# interface-board.net
KiCad netlist of a schematic drawn in EAGLE
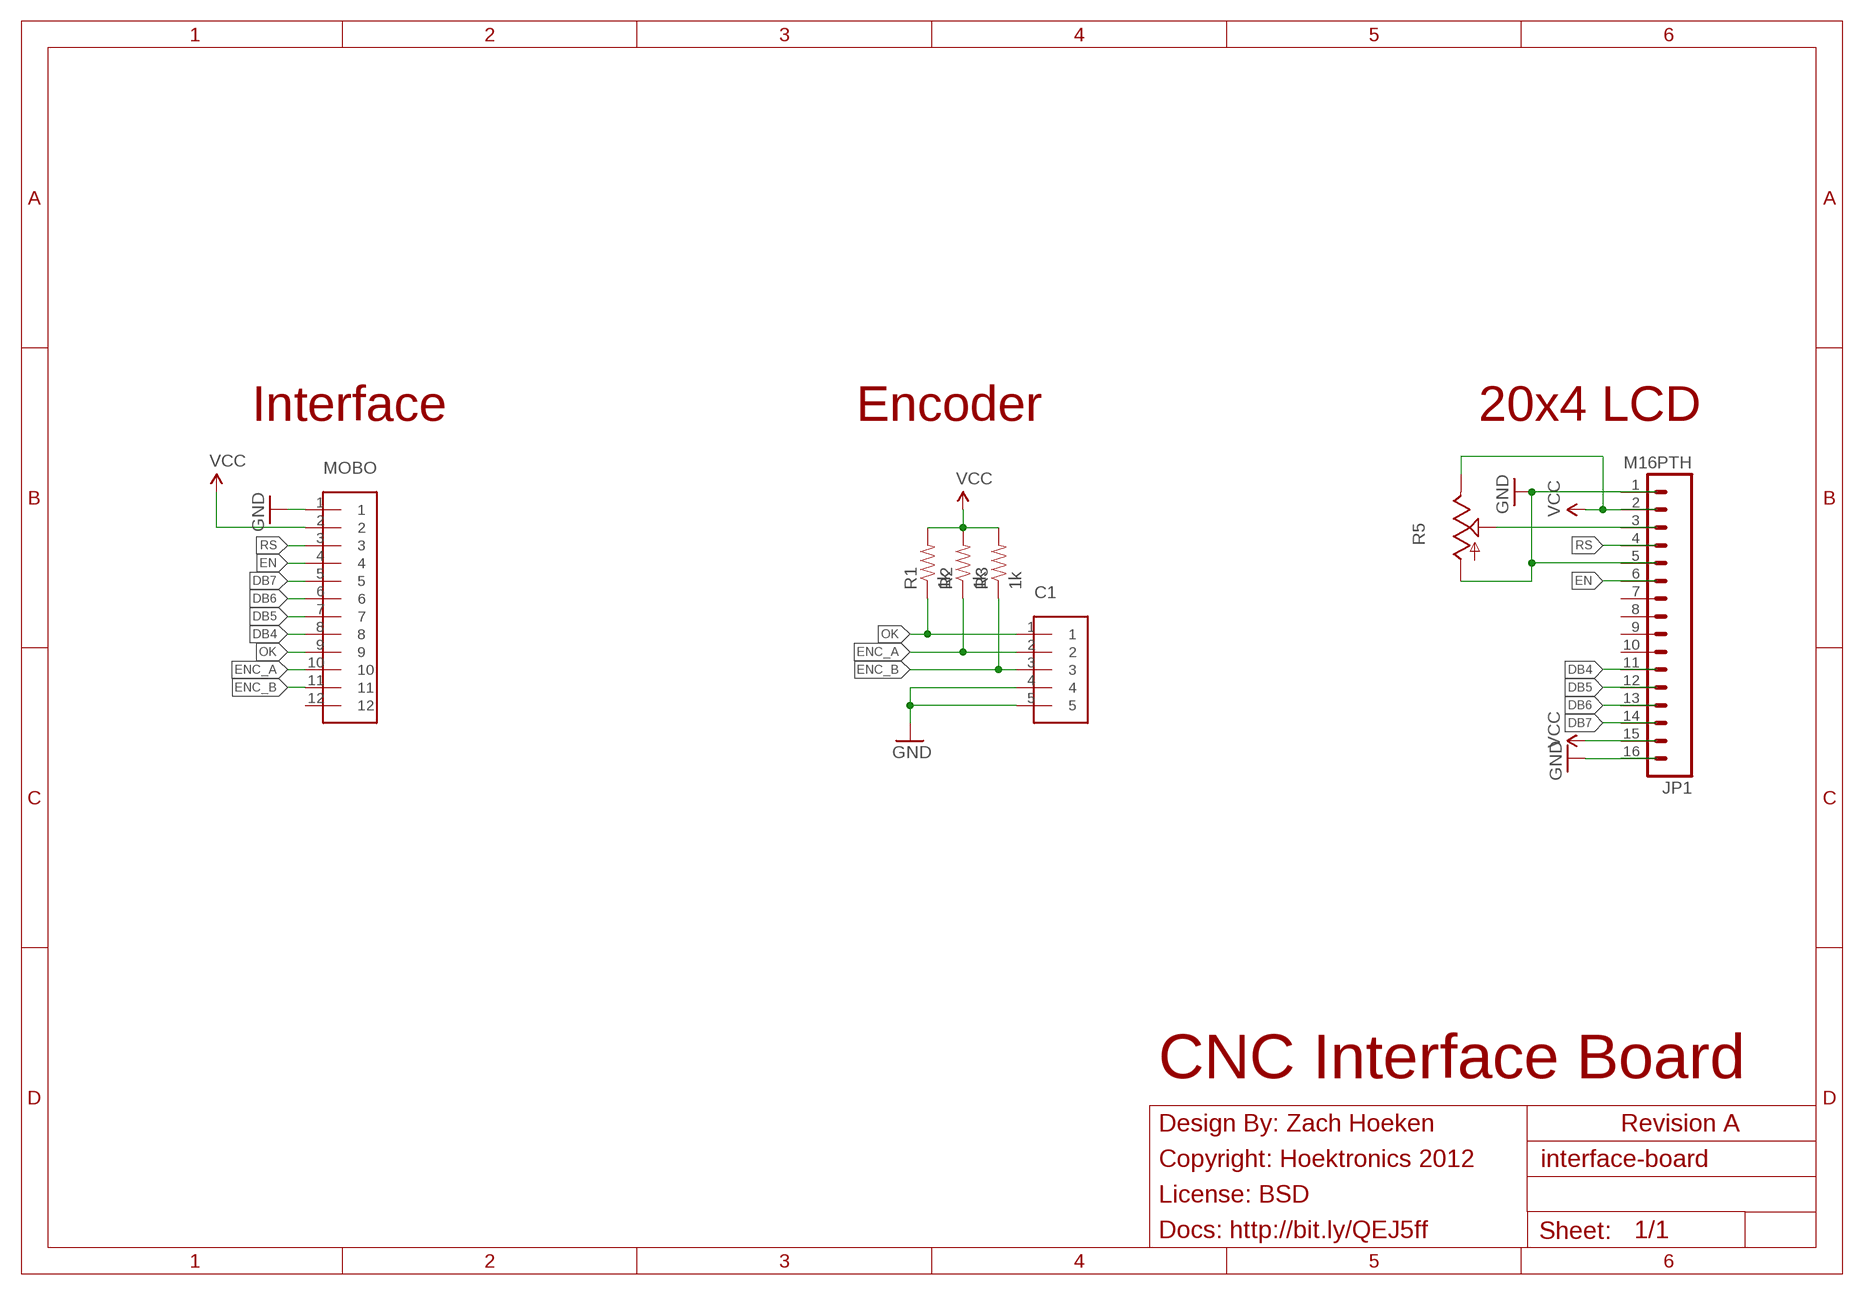
[diagram p0: schematic, sheet 1]

(export (version "E")
  (design (tool "Eeschema 10.0.6"))
  (components
    (comp (ref "C1")
      (value "CONN-5")
      (footprint "eagle-import:XH-5")
      (libsource (lib "eagle-import") (part "CONN-5"))
    )
    (comp (ref "JP1")
      (value "M16PTH")
      (footprint "eagle-import:1X16")
      (libsource (lib "eagle-import") (part "M16PTH"))
    )
    (comp (ref "MOBO")
      (value "CONN-12")
      (footprint "eagle-import:XH-12")
      (libsource (lib "eagle-import") (part "CONN-12"))
    )
    (comp (ref "R1")
      (value "1k")
      (footprint "eagle-import:0805-RC")
      (libsource (lib "eagle-import") (part "RESISTOR0805"))
    )
    (comp (ref "R2")
      (value "1k")
      (footprint "eagle-import:0805-RC")
      (libsource (lib "eagle-import") (part "RESISTOR0805"))
    )
    (comp (ref "R3")
      (value "1k")
      (footprint "eagle-import:0805-RC")
      (libsource (lib "eagle-import") (part "RESISTOR0805"))
    )
    (comp (ref "R5")
      (value "TRIM_US-B25P")
      (footprint "eagle-import:B25P")
      (libsource (lib "eagle-import") (part "TRIM_US-B25P"))
    )
  )
  (nets
    (net (code "1") (name "DB4") (class "Default")
      (node (ref "JP1") (pin "11") (pinfunction "11_11") (pintype "passive"))
      (node (ref "MOBO") (pin "8") (pinfunction "8_8") (pintype "bidirectional"))
    )
    (net (code "2") (name "DB5") (class "Default")
      (node (ref "JP1") (pin "12") (pinfunction "12_12") (pintype "passive"))
      (node (ref "MOBO") (pin "7") (pinfunction "7_7") (pintype "bidirectional"))
    )
    (net (code "3") (name "DB6") (class "Default")
      (node (ref "JP1") (pin "13") (pinfunction "13_13") (pintype "passive"))
      (node (ref "MOBO") (pin "6") (pinfunction "6_6") (pintype "bidirectional"))
    )
    (net (code "4") (name "DB7") (class "Default")
      (node (ref "JP1") (pin "14") (pinfunction "14_14") (pintype "passive"))
      (node (ref "MOBO") (pin "5") (pinfunction "5_5") (pintype "bidirectional"))
    )
    (net (code "5") (name "EN") (class "Default")
      (node (ref "JP1") (pin "6") (pinfunction "6_6") (pintype "passive"))
      (node (ref "MOBO") (pin "4") (pinfunction "4_4") (pintype "bidirectional"))
    )
    (net (code "6") (name "ENC_A") (class "Default")
      (node (ref "C1") (pin "2") (pinfunction "2_2") (pintype "bidirectional"))
      (node (ref "MOBO") (pin "10") (pinfunction "10_10") (pintype "bidirectional"))
      (node (ref "R2") (pin "1") (pinfunction "1_1") (pintype "passive"))
    )
    (net (code "7") (name "ENC_B") (class "Default")
      (node (ref "C1") (pin "3") (pinfunction "3_3") (pintype "bidirectional"))
      (node (ref "MOBO") (pin "11") (pinfunction "11_11") (pintype "bidirectional"))
      (node (ref "R3") (pin "1") (pinfunction "1_1") (pintype "passive"))
    )
    (net (code "8") (name "GND") (class "Default")
      (node (ref "C1") (pin "4") (pinfunction "4_4") (pintype "bidirectional"))
      (node (ref "C1") (pin "5") (pinfunction "5_5") (pintype "bidirectional"))
      (node (ref "JP1") (pin "1") (pinfunction "1_1") (pintype "passive"))
      (node (ref "JP1") (pin "16") (pinfunction "16_16") (pintype "passive"))
      (node (ref "JP1") (pin "5") (pinfunction "5_5") (pintype "passive"))
      (node (ref "MOBO") (pin "1") (pinfunction "1_1") (pintype "bidirectional"))
      (node (ref "R5") (pin "A") (pinfunction "A_A") (pintype "passive"))
    )
    (net (code "9") (name "Net-(JP1-Pad3)") (class "Default")
      (node (ref "JP1") (pin "3") (pinfunction "3_3") (pintype "passive"))
      (node (ref "R5") (pin "S") (pinfunction "S_S") (pintype "passive"))
    )
    (net (code "10") (name "OK") (class "Default")
      (node (ref "C1") (pin "1") (pinfunction "1_1") (pintype "bidirectional"))
      (node (ref "MOBO") (pin "9") (pinfunction "9_9") (pintype "bidirectional"))
      (node (ref "R1") (pin "1") (pinfunction "1_1") (pintype "passive"))
    )
    (net (code "11") (name "RS") (class "Default")
      (node (ref "JP1") (pin "4") (pinfunction "4_4") (pintype "passive"))
      (node (ref "MOBO") (pin "3") (pinfunction "3_3") (pintype "bidirectional"))
    )
    (net (code "12") (name "VCC") (class "Default")
      (node (ref "JP1") (pin "15") (pinfunction "15_15") (pintype "passive"))
      (node (ref "JP1") (pin "2") (pinfunction "2_2") (pintype "passive"))
      (node (ref "MOBO") (pin "2") (pinfunction "2_2") (pintype "bidirectional"))
      (node (ref "R1") (pin "2") (pinfunction "2_2") (pintype "passive"))
      (node (ref "R2") (pin "2") (pinfunction "2_2") (pintype "passive"))
      (node (ref "R3") (pin "2") (pinfunction "2_2") (pintype "passive"))
      (node (ref "R5") (pin "E") (pinfunction "E_E") (pintype "passive"))
    )
    (net (code "13") (name "unconnected-(JP1-Pad7)") (class "Default")
      (node (ref "JP1") (pin "7") (pinfunction "7_7") (pintype "passive"))
    )
    (net (code "14") (name "unconnected-(JP1-Pad8)") (class "Default")
      (node (ref "JP1") (pin "8") (pinfunction "8_8") (pintype "passive"))
    )
    (net (code "15") (name "unconnected-(JP1-Pad9)") (class "Default")
      (node (ref "JP1") (pin "9") (pinfunction "9_9") (pintype "passive"))
    )
    (net (code "16") (name "unconnected-(JP1-Pad10)") (class "Default")
      (node (ref "JP1") (pin "10") (pinfunction "10_10") (pintype "passive"))
    )
    (net (code "17") (name "unconnected-(MOBO-Pad12)") (class "Default")
      (node (ref "MOBO") (pin "12") (pinfunction "12_12") (pintype "bidirectional"))
    )
  )
)
